# DMX-A.net
KiCad netlist of a schematic drawn in EAGLE
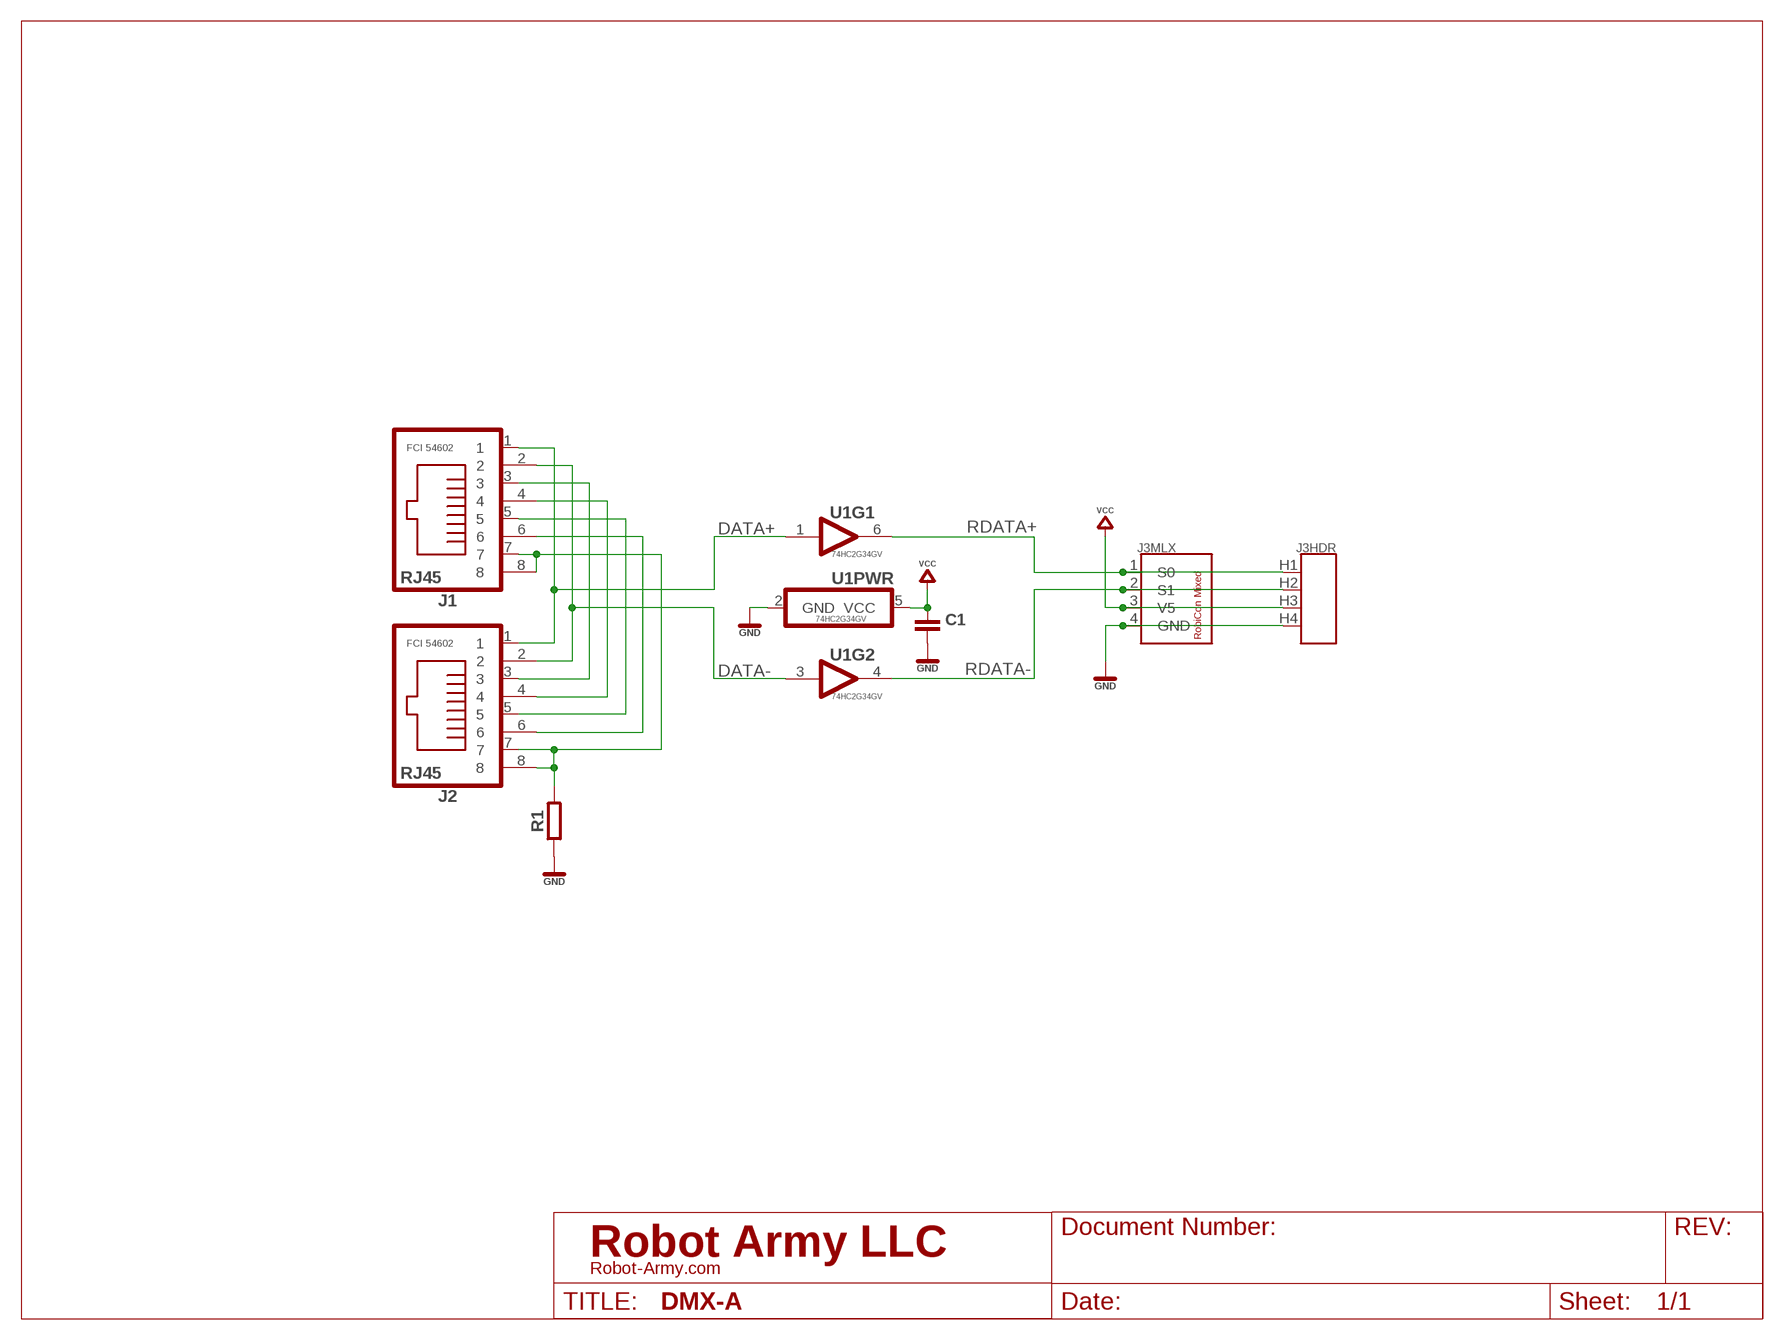
[diagram p0: schematic, sheet 1]

(export (version "E")
  (design (tool "Eeschema 10.0.6"))
  (components
    (comp (ref "C1")
      (value "CAPACITOR0603")
      (footprint "eagle-import:0603")
      (libsource (lib "eagle-import") (part "CAPACITOR0603"))
    )
    (comp (ref "J1")
      (value "FCI 54602")
      (footprint "eagle-import:FCI_54602")
      (libsource (lib "eagle-import") (part "RJ45FCI_54602"))
    )
    (comp (ref "J2")
      (value "FCI 54602")
      (footprint "eagle-import:FCI_54602")
      (libsource (lib "eagle-import") (part "RJ45FCI_54602"))
    )
    (comp (ref "J3")
      (value "ROBICON_M_04P_DUAL")
      (footprint "eagle-import:ROBICON-DUAL-04P")
      (libsource (lib "eagle-import") (part "ROBICON_M_04P_DUAL"))
    )
    (comp (ref "R1")
      (value "RESISTOR1206")
      (footprint "eagle-import:1206")
      (libsource (lib "eagle-import") (part "RESISTOR1206"))
    )
    (comp (ref "U1")
      (value "74HC2G34GV")
      (footprint "eagle-import:TSOP-6")
      (libsource (lib "eagle-import") (part "74HC2G34GV"))
    )
  )
  (nets
    (net (code "1") (name "/DATA+") (class "Default")
      (node (ref "J1") (pin "1") (pinfunction "1_1") (pintype "bidirectional"))
      (node (ref "J2") (pin "1") (pinfunction "1_1") (pintype "bidirectional"))
      (node (ref "U1") (pin "1") (pinfunction "A_1") (pintype "bidirectional"))
    )
    (net (code "2") (name "/DATA-") (class "Default")
      (node (ref "J1") (pin "2") (pinfunction "2_2") (pintype "bidirectional"))
      (node (ref "J2") (pin "2") (pinfunction "2_2") (pintype "bidirectional"))
      (node (ref "U1") (pin "3") (pinfunction "A_3") (pintype "bidirectional"))
    )
    (net (code "3") (name "/RDATA+") (class "Default")
      (node (ref "J3") (pin "1") (pinfunction "S0_1") (pintype "bidirectional"))
      (node (ref "J3") (pin "H1") (pinfunction "1_H1") (pintype "bidirectional"))
      (node (ref "U1") (pin "6") (pinfunction "Y_6") (pintype "bidirectional"))
    )
    (net (code "4") (name "/RDATA-") (class "Default")
      (node (ref "J3") (pin "2") (pinfunction "S1_2") (pintype "bidirectional"))
      (node (ref "J3") (pin "H2") (pinfunction "2_H2") (pintype "bidirectional"))
      (node (ref "U1") (pin "4") (pinfunction "Y_4") (pintype "bidirectional"))
    )
    (net (code "5") (name "GND") (class "Default")
      (node (ref "C1") (pin "2") (pinfunction "2_2") (pintype "passive"))
      (node (ref "J3") (pin "4") (pinfunction "GND_4") (pintype "power_in"))
      (node (ref "J3") (pin "H4") (pinfunction "4_H4") (pintype "bidirectional"))
      (node (ref "R1") (pin "1") (pinfunction "1_1") (pintype "passive"))
      (node (ref "U1") (pin "2") (pinfunction "GND_2") (pintype "power_in"))
    )
    (net (code "6") (name "Net-(J1-Pad3)") (class "Default")
      (node (ref "J1") (pin "3") (pinfunction "3_3") (pintype "bidirectional"))
      (node (ref "J2") (pin "3") (pinfunction "3_3") (pintype "bidirectional"))
    )
    (net (code "7") (name "Net-(J1-Pad4)") (class "Default")
      (node (ref "J1") (pin "4") (pinfunction "4_4") (pintype "bidirectional"))
      (node (ref "J2") (pin "4") (pinfunction "4_4") (pintype "bidirectional"))
    )
    (net (code "8") (name "Net-(J1-Pad5)") (class "Default")
      (node (ref "J1") (pin "5") (pinfunction "5_5") (pintype "bidirectional"))
      (node (ref "J2") (pin "5") (pinfunction "5_5") (pintype "bidirectional"))
    )
    (net (code "9") (name "Net-(J1-Pad6)") (class "Default")
      (node (ref "J1") (pin "6") (pinfunction "6_6") (pintype "bidirectional"))
      (node (ref "J2") (pin "6") (pinfunction "6_6") (pintype "bidirectional"))
    )
    (net (code "10") (name "Net-(J1-Pad7)") (class "Default")
      (node (ref "J1") (pin "7") (pinfunction "7_7") (pintype "bidirectional"))
      (node (ref "J1") (pin "8") (pinfunction "8_8") (pintype "bidirectional"))
      (node (ref "J2") (pin "7") (pinfunction "7_7") (pintype "bidirectional"))
      (node (ref "J2") (pin "8") (pinfunction "8_8") (pintype "bidirectional"))
      (node (ref "R1") (pin "2") (pinfunction "2_2") (pintype "passive"))
    )
    (net (code "11") (name "VCC") (class "Default")
      (node (ref "C1") (pin "1") (pinfunction "1_1") (pintype "passive"))
      (node (ref "J3") (pin "3") (pinfunction "V5_3") (pintype "power_in"))
      (node (ref "J3") (pin "H3") (pinfunction "3_H3") (pintype "bidirectional"))
      (node (ref "U1") (pin "5") (pinfunction "VCC_5") (pintype "power_in"))
    )
  )
)
